# diff_demo.net
KiCad netlist of a schematic drawn in Altium Designer
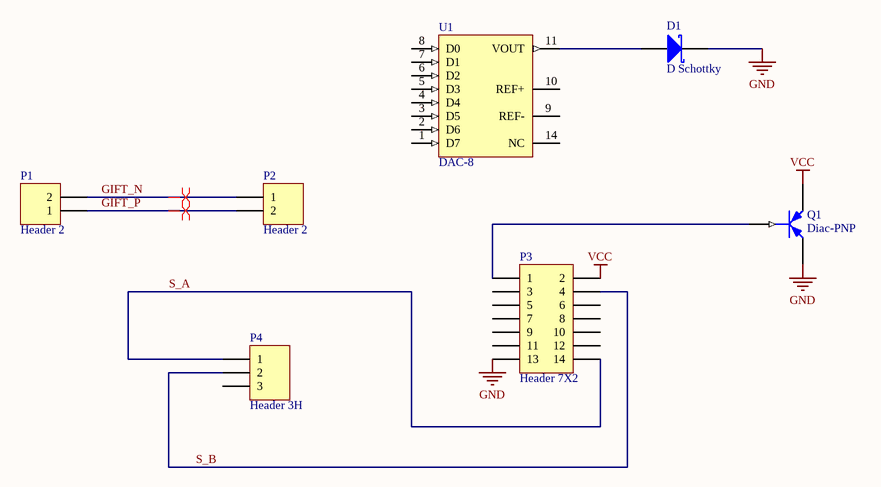
[diagram p0: diff_demo.SchDoc]

(export (version "E")
  (design (tool "Eeschema 10.0.6"))
  (components
    (comp (ref "D1")
      (value "D Schottky")
      (footprint "SMB")
      (description "Schottky Diode")
      (fields (field (name "PUBLISHER") "Altium Limited"))
      (libsource (lib "Miscellaneous Devices") (part "D Schottky"))
    )
    (comp (ref "P1")
      (value "Header 2")
      (footprint "HDR1X2")
      (description "Header, 2-Pin")
      (fields (field (name "PUBLISHER") "Altium Limited"))
      (libsource (lib "") (part "Header 2_1"))
    )
    (comp (ref "P2")
      (value "Header 2")
      (footprint "HDR1X2")
      (description "Header, 2-Pin")
      (fields (field (name "PUBLISHER") "Altium Limited"))
      (libsource (lib "Miscellaneous Connectors") (part "Header 2"))
    )
    (comp (ref "P3")
      (value "Header 7X2")
      (footprint "HDR2X7")
      (description "Header, 7-Pin, Dual row")
      (fields (field (name "PUBLISHER") "Altium Limited"))
      (libsource (lib "Miscellaneous Connectors") (part "Header 7X2"))
    )
    (comp (ref "P4")
      (value "Header 3H")
      (footprint "HDR1X3H")
      (description "Header, 3-Pin, Right Angle")
      (fields (field (name "PUBLISHER") "Altium Limited"))
      (libsource (lib "Miscellaneous Connectors") (part "Header 3H"))
    )
    (comp (ref "Q1")
      (value "Diac-PNP")
      (footprint "SOT89L")
      (description "DIAC")
      (fields (field (name "PUBLISHER") "Altium Limited"))
      (libsource (lib "Miscellaneous Devices") (part "Diac-PNP"))
    )
    (comp (ref "U1")
      (value "DAC-8")
      (footprint "SOT402-1_L")
      (description "Generic 8-Bit D/A Converter")
      (fields (field (name "PUBLISHER") "Altium Limited"))
      (libsource (lib "Miscellaneous Devices") (part "DAC-8"))
    )
  )
  (nets
    (net (code "1") (name "/GIFT_N") (class "Default")
      (node (ref "P1") (pin "2") (pinfunction "2_2") (pintype "passive"))
      (node (ref "P2") (pin "1") (pinfunction "1_1") (pintype "passive"))
    )
    (net (code "2") (name "/GIFT_P") (class "Default")
      (node (ref "P1") (pin "1") (pinfunction "1_1") (pintype "passive"))
      (node (ref "P2") (pin "2") (pinfunction "2_2") (pintype "passive"))
    )
    (net (code "3") (name "/S_A") (class "Default")
      (node (ref "P3") (pin "14") (pinfunction "14_14") (pintype "passive"))
      (node (ref "P4") (pin "1") (pinfunction "1_1") (pintype "passive"))
    )
    (net (code "4") (name "/S_B") (class "Default")
      (node (ref "P3") (pin "4") (pinfunction "4_4") (pintype "passive"))
      (node (ref "P4") (pin "2") (pinfunction "2_2") (pintype "passive"))
    )
    (net (code "5") (name "GND") (class "Default")
      (node (ref "D1") (pin "2") (pinfunction "K_2") (pintype "passive"))
      (node (ref "P3") (pin "13") (pinfunction "13_13") (pintype "passive"))
      (node (ref "Q1") (pin "3") (pinfunction "C_3") (pintype "passive"))
      (node (ref "U1") (pin "12") (pinfunction "GND_12") (pintype "power_in"))
    )
    (net (code "6") (name "Net-(D1-A)") (class "Default")
      (node (ref "D1") (pin "1") (pinfunction "A_1") (pintype "passive"))
      (node (ref "U1") (pin "11") (pinfunction "VOUT_11") (pintype "output"))
    )
    (net (code "7") (name "Net-(Q1-B)") (class "Default")
      (node (ref "P3") (pin "1") (pinfunction "1_1") (pintype "passive"))
      (node (ref "Q1") (pin "1") (pinfunction "B_1") (pintype "input"))
    )
    (net (code "8") (name "VCC") (class "Default")
      (node (ref "P3") (pin "2") (pinfunction "2_2") (pintype "passive"))
      (node (ref "Q1") (pin "2") (pinfunction "E_2") (pintype "passive"))
      (node (ref "U1") (pin "13") (pinfunction "VCC_13") (pintype "power_in"))
    )
    (net (code "9") (name "unconnected-(P3-Pad3)") (class "Default")
      (node (ref "P3") (pin "3") (pinfunction "3_3") (pintype "passive"))
    )
    (net (code "10") (name "unconnected-(P3-Pad5)") (class "Default")
      (node (ref "P3") (pin "5") (pinfunction "5_5") (pintype "passive"))
    )
    (net (code "11") (name "unconnected-(P3-Pad6)") (class "Default")
      (node (ref "P3") (pin "6") (pinfunction "6_6") (pintype "passive"))
    )
    (net (code "12") (name "unconnected-(P3-Pad7)") (class "Default")
      (node (ref "P3") (pin "7") (pinfunction "7_7") (pintype "passive"))
    )
    (net (code "13") (name "unconnected-(P3-Pad8)") (class "Default")
      (node (ref "P3") (pin "8") (pinfunction "8_8") (pintype "passive"))
    )
    (net (code "14") (name "unconnected-(P3-Pad9)") (class "Default")
      (node (ref "P3") (pin "9") (pinfunction "9_9") (pintype "passive"))
    )
    (net (code "15") (name "unconnected-(P3-Pad10)") (class "Default")
      (node (ref "P3") (pin "10") (pinfunction "10_10") (pintype "passive"))
    )
    (net (code "16") (name "unconnected-(P3-Pad11)") (class "Default")
      (node (ref "P3") (pin "11") (pinfunction "11_11") (pintype "passive"))
    )
    (net (code "17") (name "unconnected-(P3-Pad12)") (class "Default")
      (node (ref "P3") (pin "12") (pinfunction "12_12") (pintype "passive"))
    )
    (net (code "18") (name "unconnected-(P4-Pad3)") (class "Default")
      (node (ref "P4") (pin "3") (pinfunction "3_3") (pintype "passive"))
    )
    (net (code "19") (name "unconnected-(U1-D0-Pad8)") (class "Default")
      (node (ref "U1") (pin "8") (pinfunction "D0_8") (pintype "input"))
    )
    (net (code "20") (name "unconnected-(U1-D1-Pad7)") (class "Default")
      (node (ref "U1") (pin "7") (pinfunction "D1_7") (pintype "input"))
    )
    (net (code "21") (name "unconnected-(U1-D2-Pad6)") (class "Default")
      (node (ref "U1") (pin "6") (pinfunction "D2_6") (pintype "input"))
    )
    (net (code "22") (name "unconnected-(U1-D3-Pad5)") (class "Default")
      (node (ref "U1") (pin "5") (pinfunction "D3_5") (pintype "input"))
    )
    (net (code "23") (name "unconnected-(U1-D4-Pad4)") (class "Default")
      (node (ref "U1") (pin "4") (pinfunction "D4_4") (pintype "input"))
    )
    (net (code "24") (name "unconnected-(U1-D5-Pad3)") (class "Default")
      (node (ref "U1") (pin "3") (pinfunction "D5_3") (pintype "input"))
    )
    (net (code "25") (name "unconnected-(U1-D6-Pad2)") (class "Default")
      (node (ref "U1") (pin "2") (pinfunction "D6_2") (pintype "input"))
    )
    (net (code "26") (name "unconnected-(U1-D7-Pad1)") (class "Default")
      (node (ref "U1") (pin "1") (pinfunction "D7_1") (pintype "input"))
    )
    (net (code "27") (name "unconnected-(U1-NC-Pad14)") (class "Default")
      (node (ref "U1") (pin "14") (pinfunction "NC_14") (pintype "passive"))
    )
    (net (code "28") (name "unconnected-(U1-REF+-Pad10)") (class "Default")
      (node (ref "U1") (pin "10") (pinfunction "REF+_10") (pintype "passive"))
    )
    (net (code "29") (name "unconnected-(U1-REF--Pad9)") (class "Default")
      (node (ref "U1") (pin "9") (pinfunction "REF-_9") (pintype "passive"))
    )
  )
)
